# Connectors.net
KiCad netlist of a schematic drawn in Altium Designer
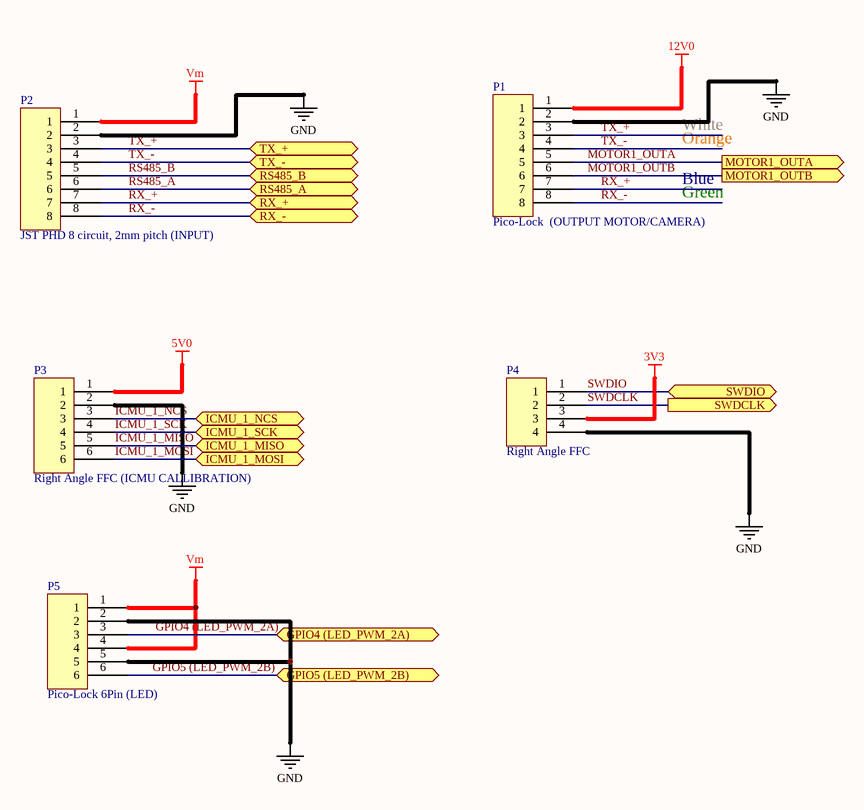
[diagram p0: Connectors.SchDoc]

(export (version "E")
  (design (tool "Eeschema 10.0.6"))
  (components
    (comp (ref "P1")
      (value "Pico-Lock  (OUTPUT MOTOR/CAMERA)")
      (footprint "5040500891")
      (description "Pico-Lock 8 circuit, 1.5mm pitch")
      (fields
        (field (name "MANUFACTURER") "Molex, LLC")
        (field (name "MANUFACTURER PART NUMBER") "5040500891")
      )
      (libsource (lib "BPL-ShematicLibrary") (part "5040500891"))
    )
    (comp (ref "P2")
      (value "JST PHD 8 circuit, 2mm pitch (INPUT)")
      (footprint "JST PHD connector")
      (description "JST PHD 8 circuit, 2mm pitch")
      (fields
        (field (name "MANUFACTURER") "JST")
        (field (name "MANUFACTURER PART NUMBER") "S8B-PHDSS(LF)(SN)")
      )
      (libsource (lib "BPL-ShematicLibrary") (part "S8B-PHDSS"))
    )
    (comp (ref "P3")
      (value "Right Angle FFC (ICMU CALLIBRATION)")
      (footprint "XF2W_0615_1A")
      (description "6 pin FFC connector,0.5mm pitch, 0.5A")
      (fields
        (field (name "MANUFACTURER") "Omron Electronics Inc-EMC Div")
        (field (name "MANUFACTURER PART NUMBER") "XF2W-0615-1A")
      )
      (libsource (lib "BPL-ShematicLibrary") (part "XF2W-0615-1A"))
    )
    (comp (ref "P4")
      (value "Right Angle FFC")
      (footprint "XF2W_0415_1A")
      (description "4 pin FFC connector,0.5mm pitch, 0.5A")
      (fields
        (field (name "MANUFACTURER") "Omron Electronics Inc-EMC Div")
        (field (name "MANUFACTURER PART NUMBER") "XF2W-0415-1A")
      )
      (libsource (lib "BPL-ShematicLibrary") (part "XF2W-0415-1A"))
    )
    (comp (ref "P5")
      (value "Pico-Lock 6Pin (LED)")
      (footprint "5040500691")
      (description "Pico-Lock 5 circuit, 1.5mm pitch")
      (fields
        (field (name "MANUFACTURER") "Molex, LLC")
        (field (name "MANUFACTURER PART NUMBER") "5040500691")
      )
      (libsource (lib "BPL-ShematicLibrary") (part "5040500691"))
    )
  )
  (nets
    (net (code "1") (name "/GPIO4 (LED_PWM_2A)") (class "Default")
      (node (ref "P5") (pin "3") (pinfunction "3_3") (pintype "passive"))
    )
    (net (code "2") (name "/GPIO5 (LED_PWM_2B)") (class "Default")
      (node (ref "P5") (pin "6") (pinfunction "6_6") (pintype "passive"))
    )
    (net (code "3") (name "/ICMU_1_MISO") (class "Default")
      (node (ref "P3") (pin "5") (pinfunction "5_5") (pintype "passive"))
    )
    (net (code "4") (name "/ICMU_1_MOSI") (class "Default")
      (node (ref "P3") (pin "6") (pinfunction "6_6") (pintype "passive"))
    )
    (net (code "5") (name "/ICMU_1_NCS") (class "Default")
      (node (ref "P3") (pin "3") (pinfunction "3_3") (pintype "passive"))
    )
    (net (code "6") (name "/ICMU_1_SCK") (class "Default")
      (node (ref "P3") (pin "4") (pinfunction "4_4") (pintype "passive"))
    )
    (net (code "7") (name "/MOTOR1_OUTA") (class "Default")
      (node (ref "P1") (pin "5") (pinfunction "5_5") (pintype "passive"))
    )
    (net (code "8") (name "/MOTOR1_OUTB") (class "Default")
      (node (ref "P1") (pin "6") (pinfunction "6_6") (pintype "passive"))
    )
    (net (code "9") (name "/RS485_A") (class "Default")
      (node (ref "P2") (pin "6") (pinfunction "6_6") (pintype "passive"))
    )
    (net (code "10") (name "/RS485_B") (class "Default")
      (node (ref "P2") (pin "5") (pinfunction "5_5") (pintype "passive"))
    )
    (net (code "11") (name "/RX_+") (class "Default")
      (node (ref "P1") (pin "7") (pinfunction "7_7") (pintype "passive"))
      (node (ref "P2") (pin "7") (pinfunction "7_7") (pintype "passive"))
    )
    (net (code "12") (name "/RX_-") (class "Default")
      (node (ref "P1") (pin "8") (pinfunction "8_8") (pintype "passive"))
      (node (ref "P2") (pin "8") (pinfunction "8_8") (pintype "passive"))
    )
    (net (code "13") (name "/SWDCLK") (class "Default")
      (node (ref "P4") (pin "2") (pinfunction "2_2") (pintype "passive"))
    )
    (net (code "14") (name "/SWDIO") (class "Default")
      (node (ref "P4") (pin "1") (pinfunction "1_1") (pintype "passive"))
    )
    (net (code "15") (name "/TX_+") (class "Default")
      (node (ref "P1") (pin "3") (pinfunction "3_3") (pintype "passive"))
      (node (ref "P2") (pin "3") (pinfunction "3_3") (pintype "passive"))
    )
    (net (code "16") (name "/TX_-") (class "Default")
      (node (ref "P1") (pin "4") (pinfunction "4_4") (pintype "passive"))
      (node (ref "P2") (pin "4") (pinfunction "4_4") (pintype "passive"))
    )
    (net (code "17") (name "3V3") (class "Default")
      (node (ref "P4") (pin "3") (pinfunction "3_3") (pintype "passive"))
    )
    (net (code "18") (name "5V0") (class "Default")
      (node (ref "P3") (pin "1") (pinfunction "1_1") (pintype "passive"))
    )
    (net (code "19") (name "12V0") (class "Default")
      (node (ref "P1") (pin "1") (pinfunction "1_1") (pintype "passive"))
    )
    (net (code "20") (name "GND") (class "Default")
      (node (ref "P1") (pin "2") (pinfunction "2_2") (pintype "passive"))
      (node (ref "P2") (pin "2") (pinfunction "2_2") (pintype "passive"))
      (node (ref "P3") (pin "2") (pinfunction "2_2") (pintype "passive"))
      (node (ref "P4") (pin "4") (pinfunction "4_4") (pintype "passive"))
      (node (ref "P5") (pin "2") (pinfunction "2_2") (pintype "passive"))
      (node (ref "P5") (pin "5") (pinfunction "5_5") (pintype "passive"))
    )
    (net (code "21") (name "Vm") (class "Default")
      (node (ref "P2") (pin "1") (pinfunction "1_1") (pintype "passive"))
      (node (ref "P5") (pin "1") (pinfunction "1_1") (pintype "passive"))
      (node (ref "P5") (pin "4") (pinfunction "4_4") (pintype "passive"))
    )
  )
)
